# Main.net
KiCad netlist of a schematic drawn in Altium Designer
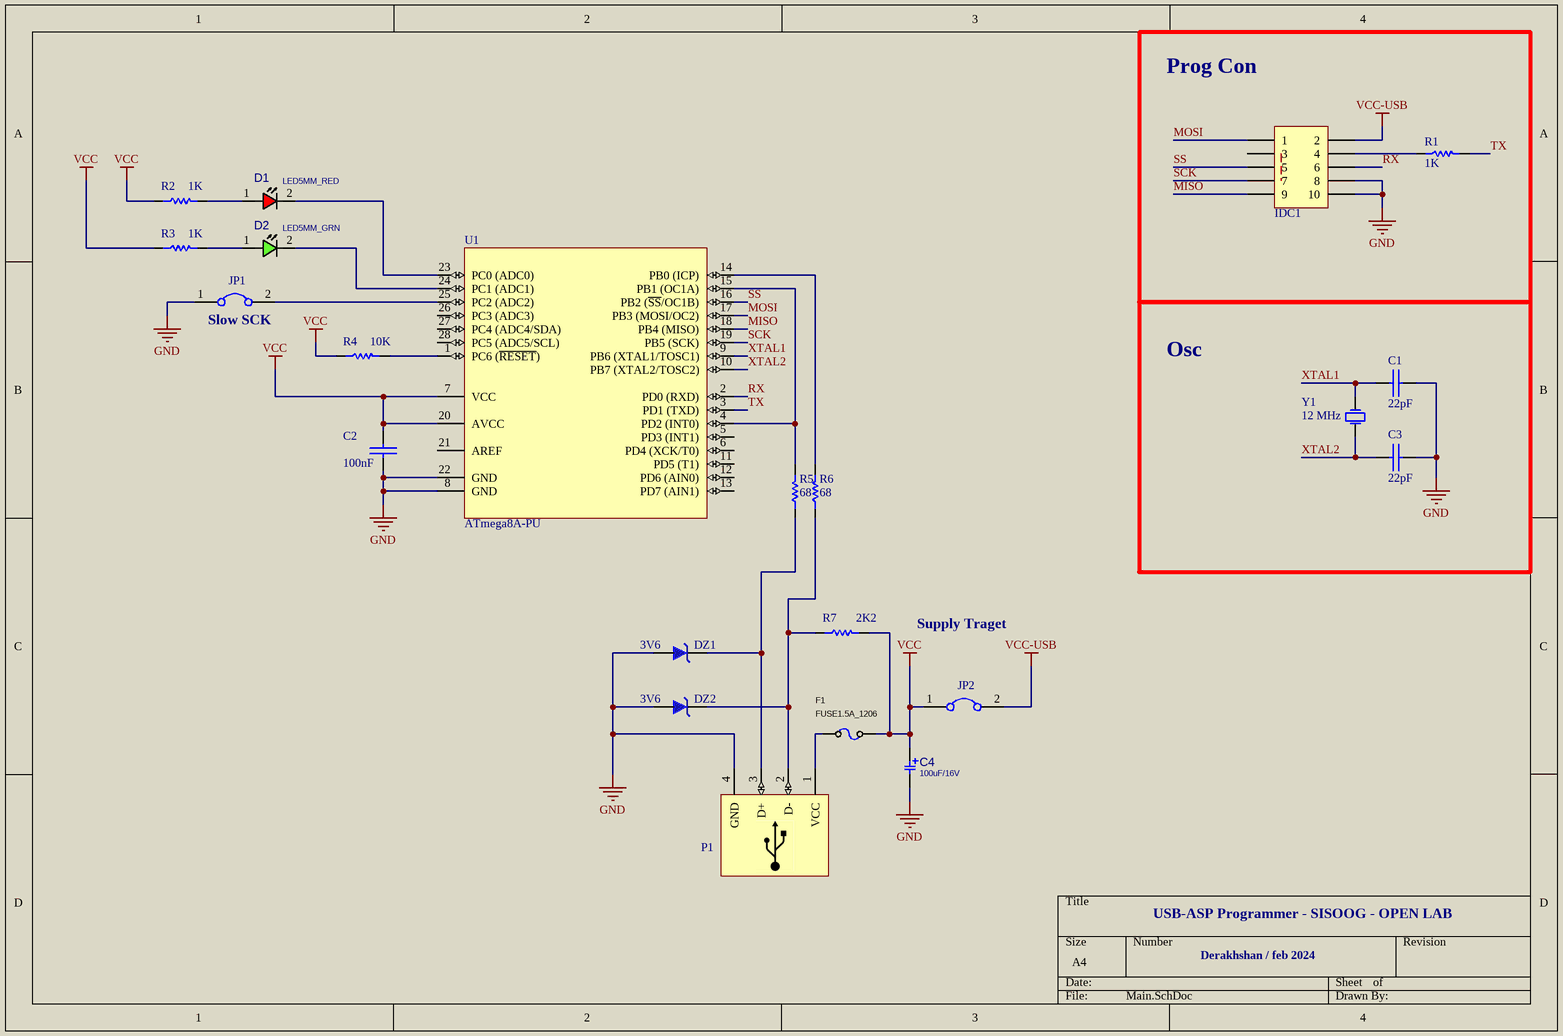
[diagram p0: Main.SchDoc]

(export (version "E")
  (design (tool "Eeschema 10.0.6"))
  (components
    (comp (ref "C1")
      (value "22pF")
      (footprint "Cap - 100nF")
      (description "Bipolar Capacitor")
      (fields (field (name "VOLTAGE") "100V") (field (name "DESIGNER") "Saeid Jorablo"))
      (libsource (lib "My Library") (part "Cap-Bipolar"))
    )
    (comp (ref "C2")
      (value "100nF")
      (footprint "Cap - 100nF")
      (description "Bipolar Capacitor")
      (fields (field (name "VOLTAGE") "100V") (field (name "DESIGNER") "Saeid Jorablo"))
      (libsource (lib "My Library") (part "Cap-Bipolar"))
    )
    (comp (ref "C3")
      (value "22pF")
      (footprint "Cap - 100nF")
      (description "Bipolar Capacitor")
      (fields (field (name "VOLTAGE") "100V") (field (name "DESIGNER") "Saeid Jorablo"))
      (libsource (lib "My Library") (part "Cap-Bipolar"))
    )
    (comp (ref "C4")
      (value "100uF/16V")
      (footprint "C_EL_5X7")
      (description "CAP, THD, ELEC,")
      (fields (field (name "MANF_P#") "MANF_PART#") (field (name "MANF") "MANF"))
      (libsource (lib "passive_thd") (part "CAP_THD_EL"))
    )
    (comp (ref "D1")
      (value "LED5MM_RED")
      (footprint "LED5MM_RED")
      (description "LED, THD, 5MM, RED")
      (fields (field (name "MANF") "MANF") (field (name "MANF_P#") "MANF_PART#"))
      (libsource (lib "led(diode)") (part "LED_THD_5MM_RED"))
    )
    (comp (ref "D2")
      (value "LED5MM_GRN")
      (footprint "LED5MM_GRN")
      (description "LED, THD, 5MM, GREEN")
      (fields (field (name "MANF") "MANF") (field (name "MANF_P#") "MANF_PART#"))
      (libsource (lib "led(diode)") (part "LED_THD_5MM_GRN"))
    )
    (comp (ref "DZ1")
      (value "3V6")
      (footprint "DO 35")
      (description "DIODE ZENER GENERAL")
      (fields (field (name "PUBLISHER") "Abbas Basereh"))
      (libsource (lib "Altium") (part "ZENER GENERAL DIODE"))
    )
    (comp (ref "DZ2")
      (value "3V6")
      (footprint "DO 35")
      (description "DIODE ZENER GENERAL")
      (fields (field (name "PUBLISHER") "Abbas Basereh"))
      (libsource (lib "Altium") (part "ZENER GENERAL DIODE"))
    )
    (comp (ref "F1")
      (value "FUSE1.5A_1206")
      (footprint "F1206")
      (description "Fuse, 3A, 32VDC, 1206, SMD, Slow Blow")
      (fields (field (name "MANF") "Bourns") (field (name "MANF_P#") "SF-1206SP300-2"))
      (libsource (lib "protect_tvs_esd_fuse") (part "FUSE_3A_1206_SLOW"))
    )
    (comp (ref "IDC1")
      (value "CONNECTOR_IDC_5X2")
      (footprint "IDC2.54-10PIN")
      (description "IDC, 5-Pin, Dual row")
      (fields
        (field (name "MANUFACTURER") "CHINA")
        (field (name "PUBLISHER") "ABBAS BASEREH")
        (field (name "DESIGNER") "ABBAS BASEREH")
      )
      (libsource (lib "Altium") (part "IDC 5X2"))
    )
    (comp (ref "JP1")
      (value "Jumper")
      (footprint "Jumper Small - 2.54 - GRAY")
      (libsource (lib "Altium") (part "Jumper"))
    )
    (comp (ref "JP2")
      (value "Jumper")
      (footprint "Jumper Small - 2.54 - GRAY")
      (libsource (lib "Altium") (part "Jumper"))
    )
    (comp (ref "P1")
      (value "USB Connector")
      (footprint "USB2.5-2H4E")
      (description "USB Connector-B Type")
      (libsource (lib "Altium") (part "USB B-Type"))
    )
    (comp (ref "R1")
      (value "1K")
      (footprint "Res-(1/4)")
      (description "Resistor")
      (libsource (lib "My Library") (part "Resistor"))
    )
    (comp (ref "R2")
      (value "1K")
      (footprint "Res-(1/4)")
      (description "Resistor")
      (libsource (lib "My Library") (part "Resistor"))
    )
    (comp (ref "R3")
      (value "1K")
      (footprint "Res-(1/4)")
      (description "Resistor")
      (libsource (lib "My Library") (part "Resistor"))
    )
    (comp (ref "R4")
      (value "10K")
      (footprint "Res-(1/4)")
      (description "Resistor")
      (libsource (lib "My Library") (part "Resistor"))
    )
    (comp (ref "R5")
      (value "68")
      (footprint "Res-(1/4)")
      (description "Resistor")
      (libsource (lib "My Library") (part "Resistor"))
    )
    (comp (ref "R6")
      (value "68")
      (footprint "Res-(1/4)")
      (description "Resistor")
      (libsource (lib "My Library") (part "Resistor"))
    )
    (comp (ref "R7")
      (value "2K2")
      (footprint "Res-(1/4)")
      (description "Resistor")
      (libsource (lib "My Library") (part "Resistor"))
    )
    (comp (ref "U1")
      (value "ATmega8A-PU")
      (footprint "28P3")
      (fields (field (name "PUBLISHER") "Abbas Basereh"))
      (libsource (lib "Altium") (part "ATmega8A-PU"))
    )
    (comp (ref "Y1")
      (value "12 MHz")
      (footprint "XTAL 16MHZ")
      (description "XTAL Crystal")
      (fields (field (name "DESIGNER") "ABBAS BASEREH"))
      (libsource (lib "Altium") (part "XTAL"))
    )
  )
  (nets
    (net (code "1") (name "/MISO") (class "Default")
      (node (ref "IDC1") (pin "9") (pinfunction "9_9") (pintype "passive"))
      (node (ref "U1") (pin "18") (pinfunction "PB4_(MISO)_18") (pintype "bidirectional"))
    )
    (net (code "2") (name "/MOSI") (class "Default")
      (node (ref "IDC1") (pin "1") (pinfunction "1_1") (pintype "passive"))
      (node (ref "U1") (pin "17") (pinfunction "PB3_(MOSI/OC2)_17") (pintype "bidirectional"))
    )
    (net (code "3") (name "/RX") (class "Default")
      (node (ref "IDC1") (pin "6") (pinfunction "6_6") (pintype "passive"))
      (node (ref "U1") (pin "2") (pinfunction "PD0_(RXD)_2") (pintype "bidirectional"))
    )
    (net (code "4") (name "/SCK") (class "Default")
      (node (ref "IDC1") (pin "7") (pinfunction "7_7") (pintype "passive"))
      (node (ref "U1") (pin "19") (pinfunction "PB5_(SCK)_19") (pintype "bidirectional"))
    )
    (net (code "5") (name "/SS") (class "Default")
      (node (ref "IDC1") (pin "5") (pinfunction "5_5") (pintype "passive"))
      (node (ref "U1") (pin "16") (pinfunction "PB2_(~{SS}/OC1B)_16") (pintype "bidirectional"))
    )
    (net (code "6") (name "/TX") (class "Default")
      (node (ref "R1") (pin "2") (pinfunction "2_2") (pintype "passive"))
      (node (ref "U1") (pin "3") (pinfunction "PD1_(TXD)_3") (pintype "bidirectional"))
    )
    (net (code "7") (name "/XTAL1") (class "Default")
      (node (ref "C1") (pin "1") (pinfunction "+_1") (pintype "passive"))
      (node (ref "U1") (pin "9") (pinfunction "PB6_(XTAL1/TOSC1)_9") (pintype "bidirectional"))
      (node (ref "Y1") (pin "1") (pinfunction "OSC1_1") (pintype "passive"))
    )
    (net (code "8") (name "/XTAL2") (class "Default")
      (node (ref "C3") (pin "1") (pinfunction "+_1") (pintype "passive"))
      (node (ref "U1") (pin "10") (pinfunction "PB7_(XTAL2/TOSC2)_10") (pintype "bidirectional"))
      (node (ref "Y1") (pin "2") (pinfunction "OSC2_2") (pintype "passive"))
    )
    (net (code "9") (name "GND") (class "Default")
      (node (ref "C1") (pin "2") (pinfunction "-_2") (pintype "passive"))
      (node (ref "C2") (pin "2") (pinfunction "-_2") (pintype "passive"))
      (node (ref "C3") (pin "2") (pinfunction "-_2") (pintype "passive"))
      (node (ref "C4") (pin "2") (pinfunction "2_2") (pintype "passive"))
      (node (ref "DZ1") (pin "1") (pintype "passive"))
      (node (ref "DZ2") (pin "1") (pintype "passive"))
      (node (ref "IDC1") (pin "10") (pinfunction "10_10") (pintype "passive"))
      (node (ref "IDC1") (pin "8") (pinfunction "8_8") (pintype "passive"))
      (node (ref "JP1") (pin "1") (pinfunction "1_1") (pintype "passive"))
      (node (ref "P1") (pin "4") (pinfunction "GND_4") (pintype "power_in"))
      (node (ref "U1") (pin "22") (pinfunction "GND_22") (pintype "power_in"))
      (node (ref "U1") (pin "8") (pinfunction "GND_8") (pintype "power_in"))
    )
    (net (code "10") (name "Net-(D1-ANODE)") (class "Default")
      (node (ref "D1") (pin "1") (pinfunction "ANODE_1") (pintype "passive"))
      (node (ref "R2") (pin "2") (pinfunction "2_2") (pintype "passive"))
    )
    (net (code "11") (name "Net-(D1-CATHODE)") (class "Default")
      (node (ref "D1") (pin "2") (pinfunction "CATHODE_2") (pintype "passive"))
      (node (ref "U1") (pin "23") (pinfunction "PC0_(ADC0)_23") (pintype "bidirectional"))
    )
    (net (code "12") (name "Net-(D2-ANODE)") (class "Default")
      (node (ref "D2") (pin "1") (pinfunction "ANODE_1") (pintype "passive"))
      (node (ref "R3") (pin "2") (pinfunction "2_2") (pintype "passive"))
    )
    (net (code "13") (name "Net-(D2-CATHODE)") (class "Default")
      (node (ref "D2") (pin "2") (pinfunction "CATHODE_2") (pintype "passive"))
      (node (ref "U1") (pin "24") (pinfunction "PC1_(ADC1)_24") (pintype "bidirectional"))
    )
    (net (code "14") (name "Net-(IDC1-Pad4)") (class "Default")
      (node (ref "IDC1") (pin "4") (pinfunction "4_4") (pintype "passive"))
      (node (ref "R1") (pin "1") (pinfunction "1_1") (pintype "passive"))
    )
    (net (code "15") (name "Net-(P1-D+)") (class "Default")
      (node (ref "DZ1") (pin "2") (pintype "passive"))
      (node (ref "P1") (pin "3") (pinfunction "D+_3") (pintype "bidirectional"))
      (node (ref "R5") (pin "1") (pinfunction "1_1") (pintype "passive"))
    )
    (net (code "16") (name "Net-(P1-D-)") (class "Default")
      (node (ref "DZ2") (pin "2") (pintype "passive"))
      (node (ref "P1") (pin "2") (pinfunction "D-_2") (pintype "bidirectional"))
      (node (ref "R6") (pin "1") (pinfunction "1_1") (pintype "passive"))
      (node (ref "R7") (pin "1") (pinfunction "1_1") (pintype "passive"))
    )
    (net (code "17") (name "Net-(P1-VCC)") (class "Default")
      (node (ref "F1") (pin "1") (pinfunction "1_1") (pintype "passive"))
      (node (ref "P1") (pin "1") (pinfunction "VCC_1") (pintype "power_in"))
    )
    (net (code "18") (name "Net-(U1-PB0_(ICP))") (class "Default")
      (node (ref "R6") (pin "2") (pinfunction "2_2") (pintype "passive"))
      (node (ref "U1") (pin "14") (pinfunction "PB0_(ICP)_14") (pintype "bidirectional"))
    )
    (net (code "19") (name "Net-(U1-PB1_(OC1A))") (class "Default")
      (node (ref "R5") (pin "2") (pinfunction "2_2") (pintype "passive"))
      (node (ref "U1") (pin "15") (pinfunction "PB1_(OC1A)_15") (pintype "bidirectional"))
      (node (ref "U1") (pin "4") (pinfunction "PD2_(INT0)_4") (pintype "bidirectional"))
    )
    (net (code "20") (name "Net-(U1-PC2_(ADC2))") (class "Default")
      (node (ref "JP1") (pin "2") (pinfunction "2_2") (pintype "passive"))
      (node (ref "U1") (pin "25") (pinfunction "PC2_(ADC2)_25") (pintype "bidirectional"))
    )
    (net (code "21") (name "Net-(U1-PC6_(~{RESET}))") (class "Default")
      (node (ref "R4") (pin "2") (pinfunction "2_2") (pintype "passive"))
      (node (ref "U1") (pin "1") (pinfunction "PC6_(~{RESET})_1") (pintype "bidirectional"))
    )
    (net (code "22") (name "VCC") (class "Default")
      (node (ref "C2") (pin "1") (pinfunction "+_1") (pintype "passive"))
      (node (ref "C4") (pin "1") (pinfunction "1_1") (pintype "passive"))
      (node (ref "F1") (pin "2") (pinfunction "2_2") (pintype "passive"))
      (node (ref "JP2") (pin "1") (pinfunction "1_1") (pintype "passive"))
      (node (ref "R2") (pin "1") (pinfunction "1_1") (pintype "passive"))
      (node (ref "R3") (pin "1") (pinfunction "1_1") (pintype "passive"))
      (node (ref "R4") (pin "1") (pinfunction "1_1") (pintype "passive"))
      (node (ref "R7") (pin "2") (pinfunction "2_2") (pintype "passive"))
      (node (ref "U1") (pin "20") (pinfunction "AVCC_20") (pintype "power_in"))
      (node (ref "U1") (pin "7") (pinfunction "VCC_7") (pintype "power_in"))
    )
    (net (code "23") (name "VCC-USB") (class "Default")
      (node (ref "IDC1") (pin "2") (pinfunction "2_2") (pintype "passive"))
      (node (ref "JP2") (pin "2") (pinfunction "2_2") (pintype "passive"))
    )
    (net (code "24") (name "unconnected-(IDC1-Pad3)") (class "Default")
      (node (ref "IDC1") (pin "3") (pinfunction "3_3") (pintype "passive"))
    )
    (net (code "25") (name "unconnected-(U1-AREF-Pad21)") (class "Default")
      (node (ref "U1") (pin "21") (pinfunction "AREF_21") (pintype "passive"))
    )
    (net (code "26") (name "unconnected-(U1-PC3_(ADC3)-Pad26)") (class "Default")
      (node (ref "U1") (pin "26") (pinfunction "PC3_(ADC3)_26") (pintype "bidirectional"))
    )
    (net (code "27") (name "unconnected-(U1-PC4_(ADC4{slash}SDA)-Pad27)") (class "Default")
      (node (ref "U1") (pin "27") (pinfunction "PC4_(ADC4/SDA)_27") (pintype "bidirectional"))
    )
    (net (code "28") (name "unconnected-(U1-PC5_(ADC5{slash}SCL)-Pad28)") (class "Default")
      (node (ref "U1") (pin "28") (pinfunction "PC5_(ADC5/SCL)_28") (pintype "bidirectional"))
    )
    (net (code "29") (name "unconnected-(U1-PD3_(INT1)-Pad5)") (class "Default")
      (node (ref "U1") (pin "5") (pinfunction "PD3_(INT1)_5") (pintype "bidirectional"))
    )
    (net (code "30") (name "unconnected-(U1-PD4_(XCK{slash}T0)-Pad6)") (class "Default")
      (node (ref "U1") (pin "6") (pinfunction "PD4_(XCK/T0)_6") (pintype "bidirectional"))
    )
    (net (code "31") (name "unconnected-(U1-PD5_(T1)-Pad11)") (class "Default")
      (node (ref "U1") (pin "11") (pinfunction "PD5_(T1)_11") (pintype "bidirectional"))
    )
    (net (code "32") (name "unconnected-(U1-PD6_(AIN0)-Pad12)") (class "Default")
      (node (ref "U1") (pin "12") (pinfunction "PD6_(AIN0)_12") (pintype "bidirectional"))
    )
    (net (code "33") (name "unconnected-(U1-PD7_(AIN1)-Pad13)") (class "Default")
      (node (ref "U1") (pin "13") (pinfunction "PD7_(AIN1)_13") (pintype "bidirectional"))
    )
  )
)
